# MD2020_02-08.net
KiCad netlist of a schematic drawn in EAGLE
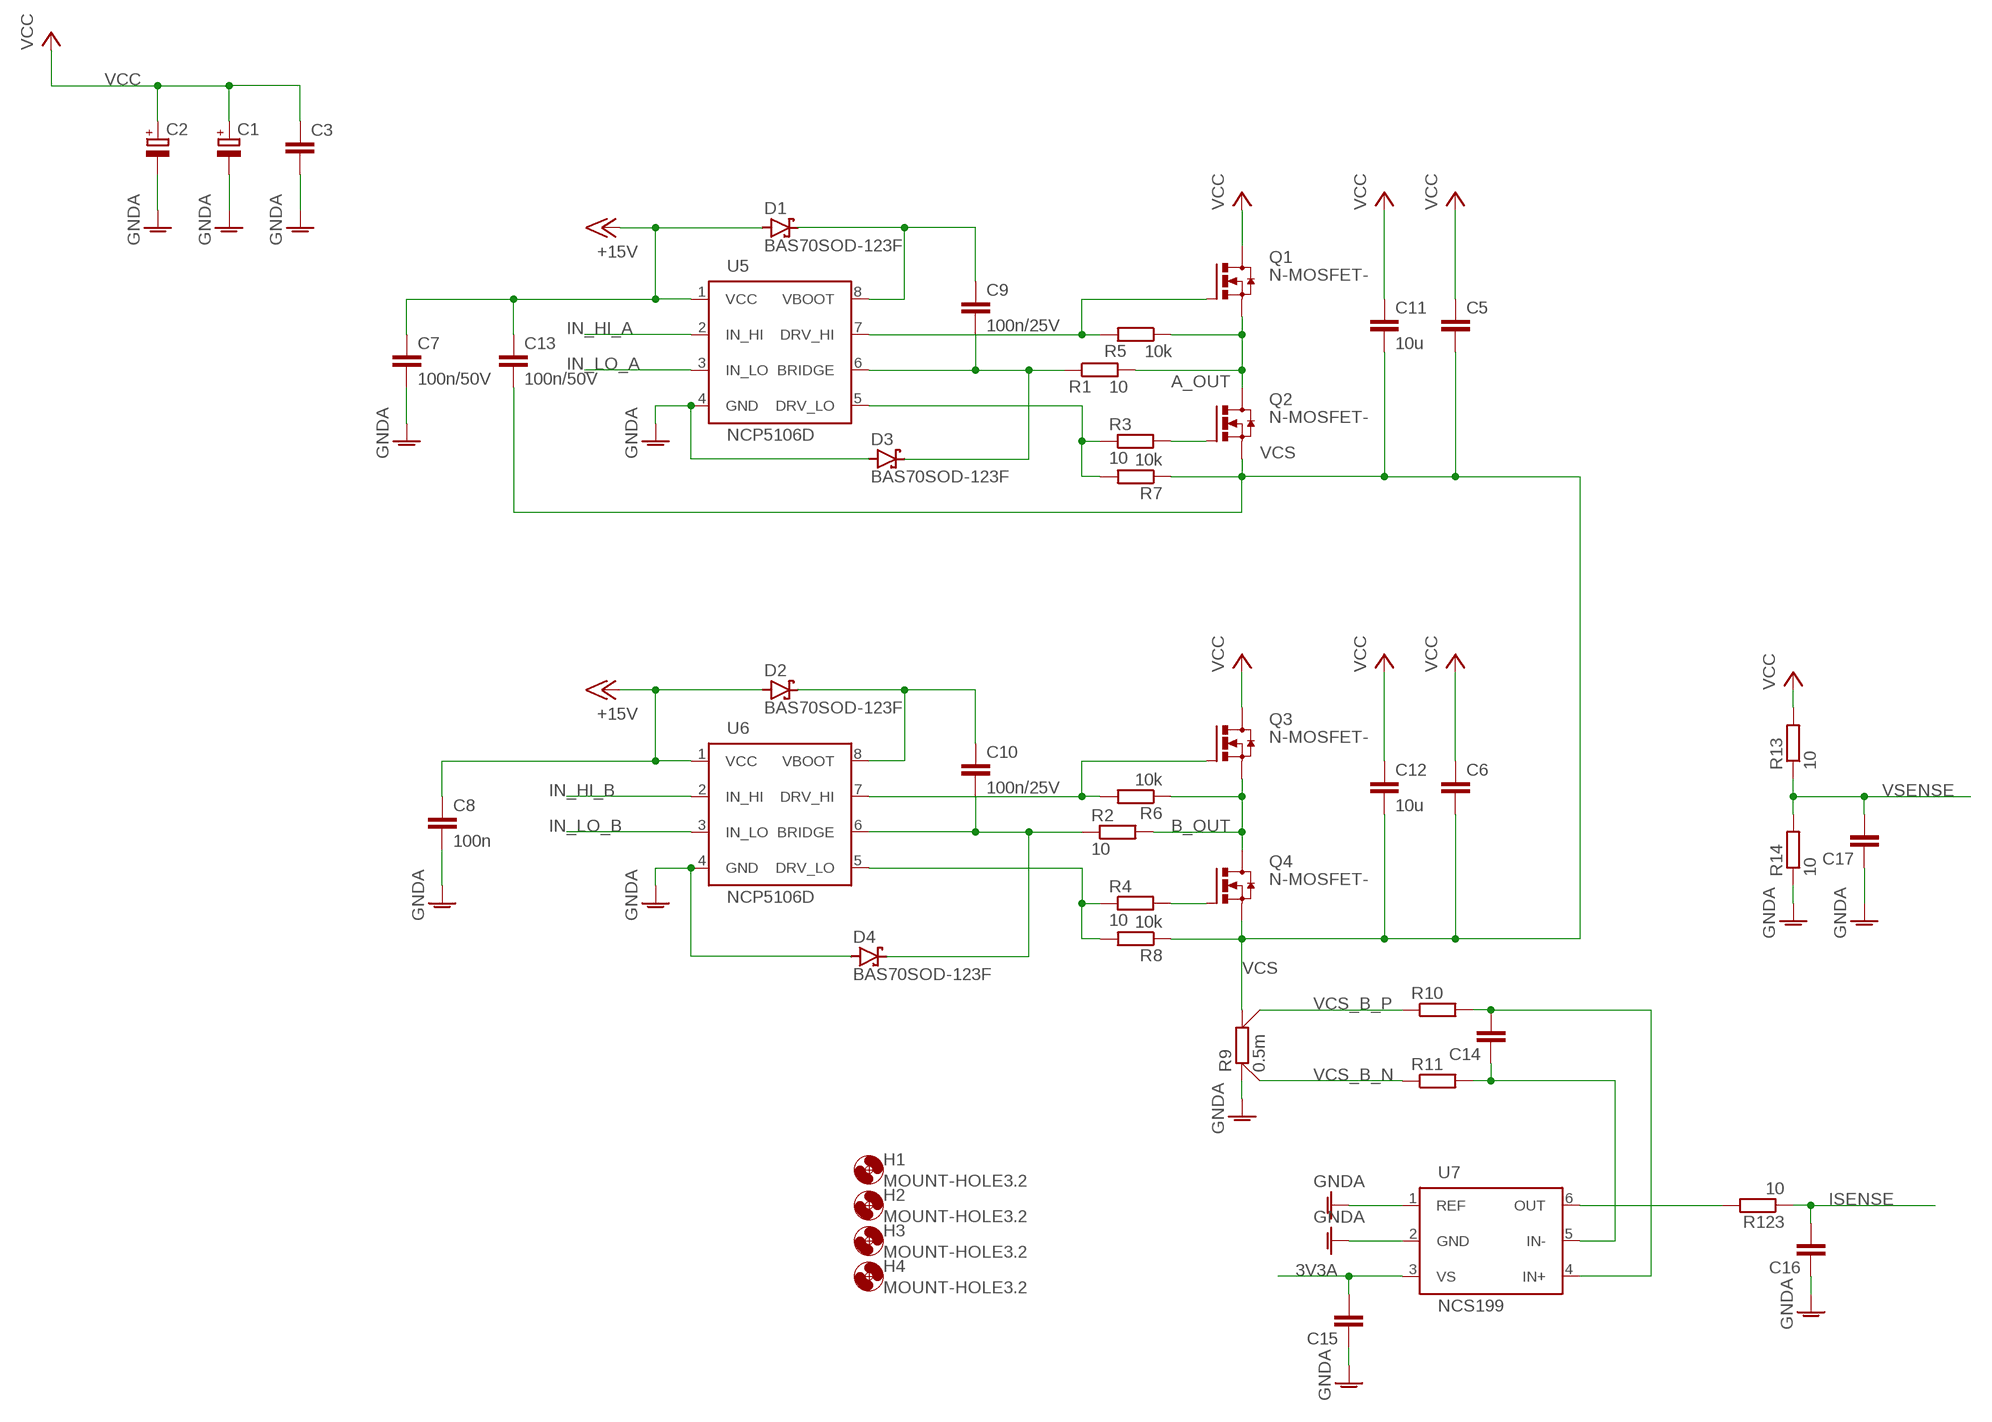
[diagram p0: schematic, sheet 1]
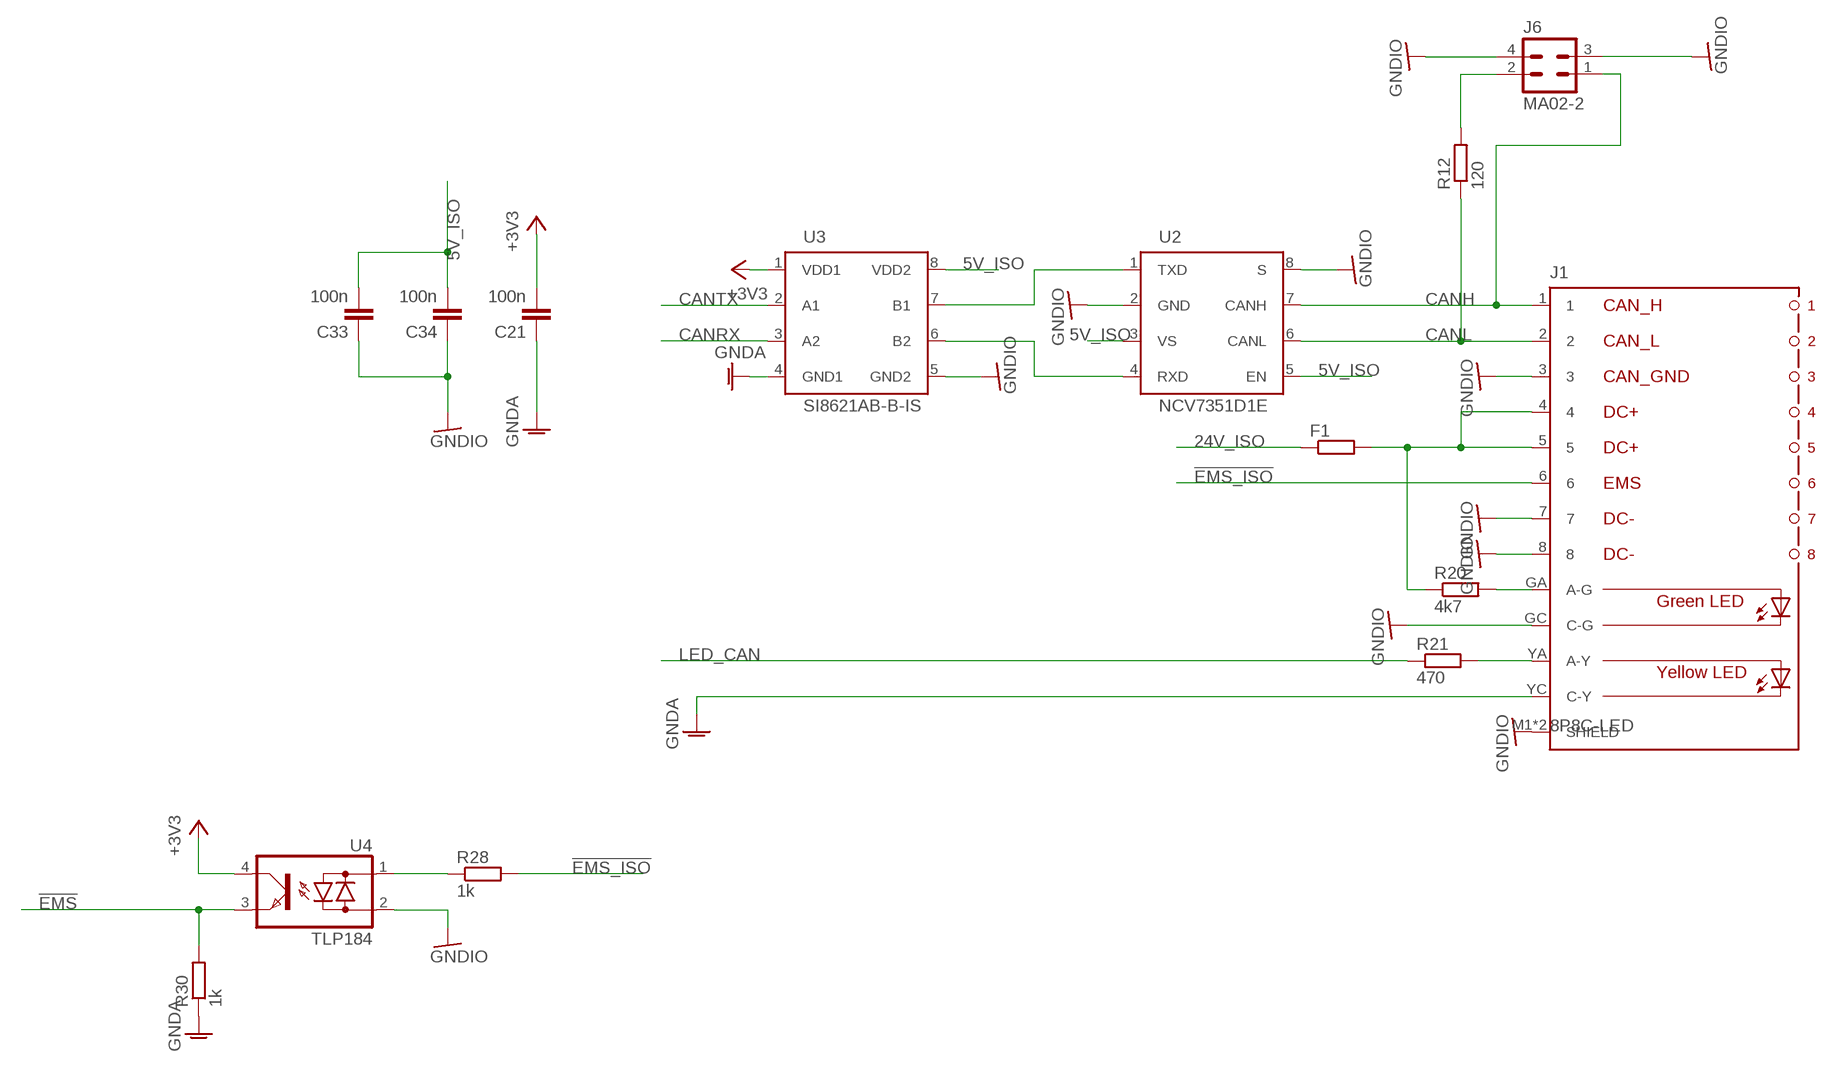
[diagram p1: schematic, sheet 2]
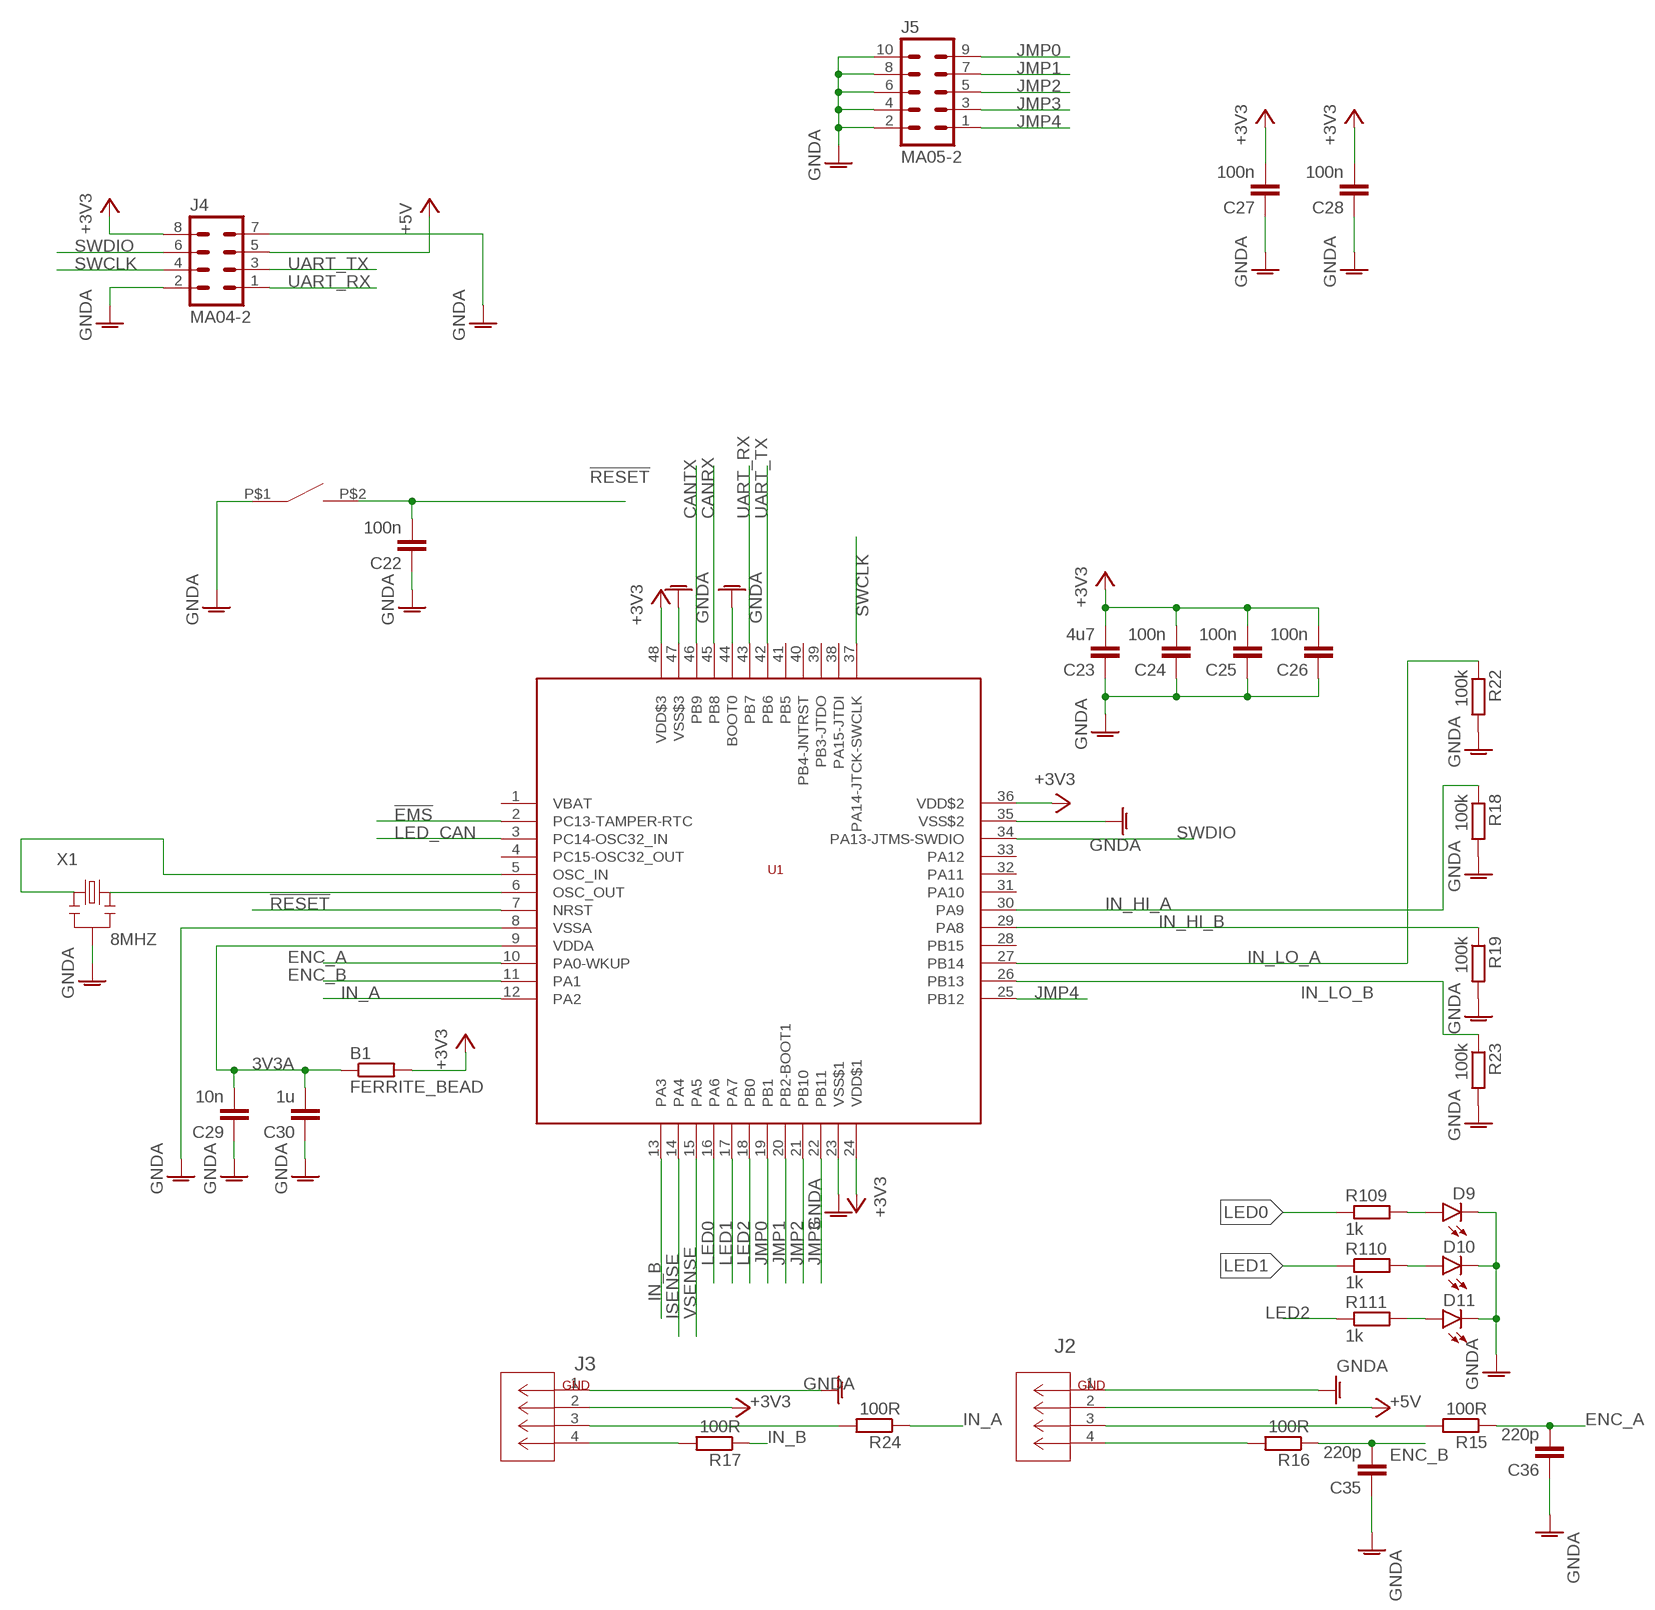
[diagram p2: schematic, sheet 3]
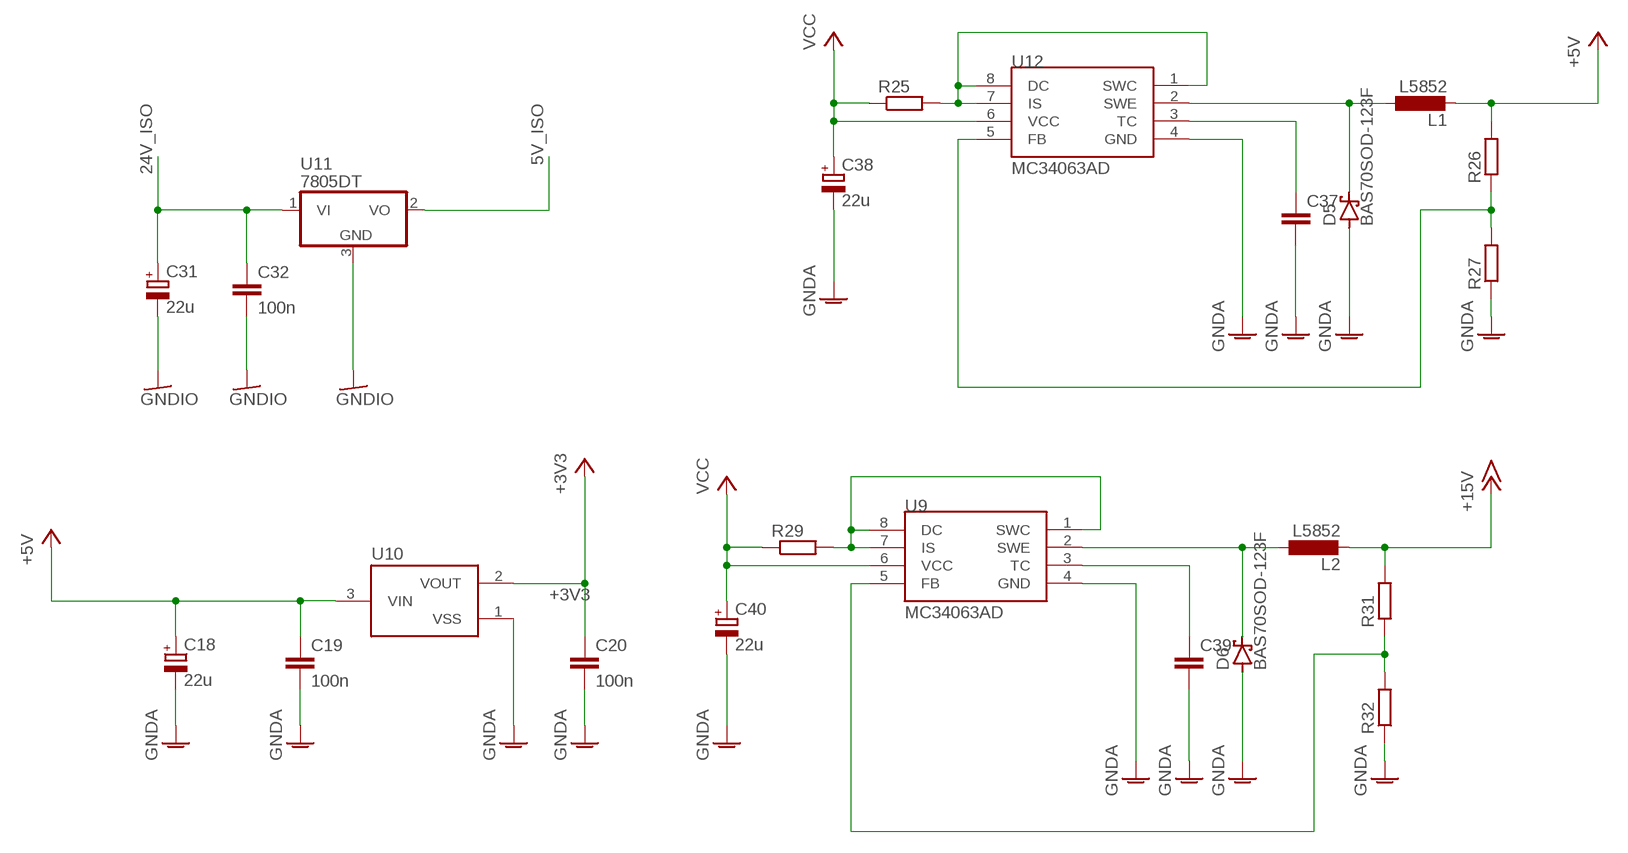
[diagram p3: schematic, sheet 4]

(export (version "E")
  (design (tool "Eeschema 10.0.6"))
  (components
    (comp (ref "C18")
      (value "22u")
      (footprint "eagle-import:E2,5-5")
      (libsource (lib "eagle-import") (part "CPOL-EUE2.5-5"))
    )
    (comp (ref "C19")
      (value "100n")
      (footprint "eagle-import:C0603")
      (libsource (lib "eagle-import") (part "C-EUC0603"))
    )
    (comp (ref "C20")
      (value "100n")
      (footprint "eagle-import:C0603")
      (libsource (lib "eagle-import") (part "C-EUC0603"))
    )
    (comp (ref "C31")
      (value "22u")
      (footprint "eagle-import:E2,5-5")
      (libsource (lib "eagle-import") (part "CPOL-EUE2.5-5"))
    )
    (comp (ref "C32")
      (value "100n")
      (footprint "eagle-import:C0603")
      (libsource (lib "eagle-import") (part "C-EUC0603"))
    )
    (comp (ref "C37")
      (value "C-EUC0603")
      (footprint "eagle-import:C0603")
      (libsource (lib "eagle-import") (part "rcl_334_C-EUC0603"))
    )
    (comp (ref "C38")
      (value "22u")
      (footprint "eagle-import:E2-5")
      (libsource (lib "eagle-import") (part "CPOL-EUE2-5"))
    )
    (comp (ref "C39")
      (value "C-EUC0603")
      (footprint "eagle-import:C0603")
      (libsource (lib "eagle-import") (part "rcl_334_C-EUC0603"))
    )
    (comp (ref "C40")
      (value "22u")
      (footprint "eagle-import:E2-5")
      (libsource (lib "eagle-import") (part "CPOL-EUE2-5"))
    )
    (comp (ref "D5")
      (value "BAS70SOD-123F")
      (footprint "eagle-import:SOD123F")
      (libsource (lib "eagle-import") (part "BAS70SOD-123F"))
    )
    (comp (ref "D6")
      (value "BAS70SOD-123F")
      (footprint "eagle-import:SOD123F")
      (libsource (lib "eagle-import") (part "BAS70SOD-123F"))
    )
    (comp (ref "L1")
      (value "L5852")
      (footprint "eagle-import:L5852")
      (libsource (lib "eagle-import") (part "L5852"))
    )
    (comp (ref "L2")
      (value "L5852")
      (footprint "eagle-import:L5852")
      (libsource (lib "eagle-import") (part "L5852"))
    )
    (comp (ref "R25")
      (value "R-EU_R0603")
      (footprint "eagle-import:R0603")
      (libsource (lib "eagle-import") (part "rcl_334_R-EU_R0603"))
    )
    (comp (ref "R26")
      (value "R-EU_R0603")
      (footprint "eagle-import:R0603")
      (libsource (lib "eagle-import") (part "rcl_334_R-EU_R0603"))
    )
    (comp (ref "R27")
      (value "R-EU_R0603")
      (footprint "eagle-import:R0603")
      (libsource (lib "eagle-import") (part "rcl_334_R-EU_R0603"))
    )
    (comp (ref "R29")
      (value "R-EU_R0603")
      (footprint "eagle-import:R0603")
      (libsource (lib "eagle-import") (part "rcl_334_R-EU_R0603"))
    )
    (comp (ref "R31")
      (value "R-EU_R0603")
      (footprint "eagle-import:R0603")
      (libsource (lib "eagle-import") (part "rcl_334_R-EU_R0603"))
    )
    (comp (ref "R32")
      (value "R-EU_R0603")
      (footprint "eagle-import:R0603")
      (libsource (lib "eagle-import") (part "rcl_334_R-EU_R0603"))
    )
    (comp (ref "U9")
      (value "MC34063AD")
      (footprint "eagle-import:SOIC8")
      (libsource (lib "eagle-import") (part "MC34063AD"))
    )
    (comp (ref "U10")
      (value "XC6206")
      (footprint "eagle-import:SOT95P240X110-3")
      (libsource (lib "eagle-import") (part "XC6206"))
    )
    (comp (ref "U11")
      (value "7805DT")
      (footprint "eagle-import:TO252")
      (libsource (lib "eagle-import") (part "78DT05"))
    )
    (comp (ref "U12")
      (value "MC34063AD")
      (footprint "eagle-import:SOIC8")
      (libsource (lib "eagle-import") (part "MC34063AD"))
    )
    (comp (ref "C1")
      (value "CPOL-EUE5-10.5")
      (footprint "eagle-import:E5-10,5")
      (libsource (lib "eagle-import") (part "CPOL-EUE5-10.5"))
    )
    (comp (ref "C2")
      (value "CPOL-EUE5-10.5")
      (footprint "eagle-import:E5-10,5")
      (libsource (lib "eagle-import") (part "CPOL-EUE5-10.5"))
    )
    (comp (ref "C3")
      (value "C-EUC0603")
      (footprint "eagle-import:C0603")
      (libsource (lib "eagle-import") (part "C-EUC0603"))
    )
    (comp (ref "C5")
      (value "C-EUC0603")
      (footprint "eagle-import:C0603")
      (libsource (lib "eagle-import") (part "C-EUC0603"))
    )
    (comp (ref "C6")
      (value "C-EUC0603")
      (footprint "eagle-import:C0603")
      (libsource (lib "eagle-import") (part "C-EUC0603"))
    )
    (comp (ref "C7")
      (value "100n/50V")
      (footprint "eagle-import:C0603")
      (libsource (lib "eagle-import") (part "C-EUC0603"))
    )
    (comp (ref "C8")
      (value "100n")
      (footprint "eagle-import:C0603")
      (libsource (lib "eagle-import") (part "C-EUC0603"))
    )
    (comp (ref "C9")
      (value "100n/25V")
      (footprint "eagle-import:C0603")
      (libsource (lib "eagle-import") (part "C-EUC0603"))
    )
    (comp (ref "C10")
      (value "100n/25V")
      (footprint "eagle-import:C0603")
      (libsource (lib "eagle-import") (part "C-EUC0603"))
    )
    (comp (ref "C11")
      (value "10u")
      (footprint "eagle-import:C1210")
      (libsource (lib "eagle-import") (part "C-EUC1210"))
    )
    (comp (ref "C12")
      (value "10u")
      (footprint "eagle-import:C1210")
      (libsource (lib "eagle-import") (part "C-EUC1210"))
    )
    (comp (ref "C13")
      (value "100n/50V")
      (footprint "eagle-import:C0603")
      (libsource (lib "eagle-import") (part "C-EUC0603"))
    )
    (comp (ref "C14")
      (value "C-EUC0603")
      (footprint "eagle-import:C0603")
      (libsource (lib "eagle-import") (part "rcl_334_C-EUC0603"))
    )
    (comp (ref "C15")
      (value "C-EUC0603")
      (footprint "eagle-import:C0603")
      (libsource (lib "eagle-import") (part "rcl_334_C-EUC0603"))
    )
    (comp (ref "C16")
      (value "C-EUC0603")
      (footprint "eagle-import:C0603")
      (libsource (lib "eagle-import") (part "rcl_334_C-EUC0603"))
    )
    (comp (ref "C17")
      (value "C-EUC0603")
      (footprint "eagle-import:C0603")
      (libsource (lib "eagle-import") (part "rcl_334_C-EUC0603"))
    )
    (comp (ref "D1")
      (value "BAS70SOD-123F")
      (footprint "eagle-import:SOD123F")
      (libsource (lib "eagle-import") (part "BAS70SOD-123F"))
    )
    (comp (ref "D2")
      (value "BAS70SOD-123F")
      (footprint "eagle-import:SOD123F")
      (libsource (lib "eagle-import") (part "BAS70SOD-123F"))
    )
    (comp (ref "D3")
      (value "BAS70SOD-123F")
      (footprint "eagle-import:SOD123F")
      (libsource (lib "eagle-import") (part "BAS70SOD-123F"))
    )
    (comp (ref "D4")
      (value "BAS70SOD-123F")
      (footprint "eagle-import:SOD123F")
      (libsource (lib "eagle-import") (part "BAS70SOD-123F"))
    )
    (comp (ref "H1")
      (value "MOUNT-HOLE3.2")
      (footprint "eagle-import:3,2")
      (libsource (lib "eagle-import") (part "MOUNT-HOLE3.2"))
    )
    (comp (ref "H2")
      (value "MOUNT-HOLE3.2")
      (footprint "eagle-import:3,2")
      (libsource (lib "eagle-import") (part "MOUNT-HOLE3.2"))
    )
    (comp (ref "H3")
      (value "MOUNT-HOLE3.2")
      (footprint "eagle-import:3,2")
      (libsource (lib "eagle-import") (part "MOUNT-HOLE3.2"))
    )
    (comp (ref "H4")
      (value "MOUNT-HOLE3.2")
      (footprint "eagle-import:3,2")
      (libsource (lib "eagle-import") (part "MOUNT-HOLE3.2"))
    )
    (comp (ref "Q1")
      (value "N-MOSFET-")
      (footprint "eagle-import:SOT669")
      (libsource (lib "eagle-import") (part "N-MOSFET-"))
    )
    (comp (ref "Q2")
      (value "N-MOSFET-")
      (footprint "eagle-import:SOT669")
      (libsource (lib "eagle-import") (part "N-MOSFET-"))
    )
    (comp (ref "Q3")
      (value "N-MOSFET-")
      (footprint "eagle-import:SOT669")
      (libsource (lib "eagle-import") (part "N-MOSFET-"))
    )
    (comp (ref "Q4")
      (value "N-MOSFET-")
      (footprint "eagle-import:SOT669")
      (libsource (lib "eagle-import") (part "N-MOSFET-"))
    )
    (comp (ref "R1")
      (value "10")
      (footprint "eagle-import:R0603")
      (libsource (lib "eagle-import") (part "R-EU_R0603"))
    )
    (comp (ref "R2")
      (value "10")
      (footprint "eagle-import:R0603")
      (libsource (lib "eagle-import") (part "R-EU_R0603"))
    )
    (comp (ref "R3")
      (value "10")
      (footprint "eagle-import:R0603")
      (libsource (lib "eagle-import") (part "R-EU_R0603"))
    )
    (comp (ref "R4")
      (value "10")
      (footprint "eagle-import:R0603")
      (libsource (lib "eagle-import") (part "R-EU_R0603"))
    )
    (comp (ref "R5")
      (value "10k")
      (footprint "eagle-import:R0603")
      (libsource (lib "eagle-import") (part "R-EU_R0603"))
    )
    (comp (ref "R6")
      (value "10k")
      (footprint "eagle-import:R0603")
      (libsource (lib "eagle-import") (part "R-EU_R0603"))
    )
    (comp (ref "R7")
      (value "10k")
      (footprint "eagle-import:R0603")
      (libsource (lib "eagle-import") (part "R-EU_R0603"))
    )
    (comp (ref "R8")
      (value "10k")
      (footprint "eagle-import:R0603")
      (libsource (lib "eagle-import") (part "R-EU_R0603"))
    )
    (comp (ref "R9")
      (value "0.5m")
      (footprint "eagle-import:CSS2H-2512")
      (libsource (lib "eagle-import") (part "CSS2H-2512"))
    )
    (comp (ref "R10")
      (value "R-EU_R0603")
      (footprint "eagle-import:R0603")
      (libsource (lib "eagle-import") (part "rcl_334_R-EU_R0603"))
    )
    (comp (ref "R11")
      (value "R-EU_R0603")
      (footprint "eagle-import:R0603")
      (libsource (lib "eagle-import") (part "rcl_334_R-EU_R0603"))
    )
    (comp (ref "R13")
      (value "10")
      (footprint "eagle-import:R0603")
      (libsource (lib "eagle-import") (part "R-EU_R0603"))
    )
    (comp (ref "R14")
      (value "10")
      (footprint "eagle-import:R0603")
      (libsource (lib "eagle-import") (part "R-EU_R0603"))
    )
    (comp (ref "R123")
      (value "10")
      (footprint "eagle-import:R0603")
      (libsource (lib "eagle-import") (part "R-EU_R0603"))
    )
    (comp (ref "U5")
      (value "NCP5106D")
      (footprint "eagle-import:SOIC127P600X175-8")
      (libsource (lib "eagle-import") (part "NCP5106D"))
    )
    (comp (ref "U6")
      (value "NCP5106D")
      (footprint "eagle-import:SOIC127P600X175-8")
      (libsource (lib "eagle-import") (part "NCP5106D"))
    )
    (comp (ref "U7")
      (value "NCS199")
      (footprint "eagle-import:SOT65P210X110-6")
      (libsource (lib "eagle-import") (part "NCS199"))
    )
    (comp (ref "B1")
      (value "FERRITE_BEAD")
      (footprint "eagle-import:R0603")
      (libsource (lib "eagle-import") (part "R-EU_R0603"))
    )
    (comp (ref "C22")
      (value "100n")
      (footprint "eagle-import:C0603")
      (libsource (lib "eagle-import") (part "C-EUC0603"))
    )
    (comp (ref "C23")
      (value "4u7")
      (footprint "eagle-import:C0805")
      (libsource (lib "eagle-import") (part "C-EUC0805"))
    )
    (comp (ref "C24")
      (value "100n")
      (footprint "eagle-import:C0603")
      (libsource (lib "eagle-import") (part "C-EUC0603"))
    )
    (comp (ref "C25")
      (value "100n")
      (footprint "eagle-import:C0603")
      (libsource (lib "eagle-import") (part "C-EUC0603"))
    )
    (comp (ref "C26")
      (value "100n")
      (footprint "eagle-import:C0603")
      (libsource (lib "eagle-import") (part "C-EUC0603"))
    )
    (comp (ref "C27")
      (value "100n")
      (footprint "eagle-import:C0603")
      (libsource (lib "eagle-import") (part "C-EUC0603"))
    )
    (comp (ref "C28")
      (value "100n")
      (footprint "eagle-import:C0603")
      (libsource (lib "eagle-import") (part "C-EUC0603"))
    )
    (comp (ref "C29")
      (value "10n")
      (footprint "eagle-import:C0603")
      (libsource (lib "eagle-import") (part "C-EUC0603"))
    )
    (comp (ref "C30")
      (value "1u")
      (footprint "eagle-import:C0603")
      (libsource (lib "eagle-import") (part "C-EUC0603"))
    )
    (comp (ref "C35")
      (value "220p")
      (footprint "eagle-import:C0603")
      (libsource (lib "eagle-import") (part "C-EUC0603"))
    )
    (comp (ref "C36")
      (value "220p")
      (footprint "eagle-import:C0603")
      (libsource (lib "eagle-import") (part "C-EUC0603"))
    )
    (comp (ref "D9")
      (value "LEDCHIPLED_0805")
      (footprint "eagle-import:CHIPLED_0805")
      (libsource (lib "eagle-import") (part "LEDCHIPLED_0805"))
    )
    (comp (ref "D10")
      (value "LEDCHIPLED_0805")
      (footprint "eagle-import:CHIPLED_0805")
      (libsource (lib "eagle-import") (part "LEDCHIPLED_0805"))
    )
    (comp (ref "D11")
      (value "LEDCHIPLED_0805")
      (footprint "eagle-import:CHIPLED_0805")
      (libsource (lib "eagle-import") (part "LEDCHIPLED_0805"))
    )
    (comp (ref "J2")
      (value "1744426-4")
      (footprint "eagle-import:CONN4_1744426-4")
      (fields (field (name "MANUFACTURER_PART_NUMBER") "17444264"))
      (libsource (lib "eagle-import") (part "1744426-4"))
    )
    (comp (ref "J3")
      (value "1744426-4")
      (footprint "eagle-import:CONN4_1744426-4")
      (fields (field (name "MANUFACTURER_PART_NUMBER") "17444264"))
      (libsource (lib "eagle-import") (part "1744426-4"))
    )
    (comp (ref "J4")
      (value "MA04-2")
      (footprint "eagle-import:MA04-2W")
      (libsource (lib "eagle-import") (part "MA04-2"))
    )
    (comp (ref "J5")
      (value "MA05-2")
      (footprint "eagle-import:MA05-2W")
      (libsource (lib "eagle-import") (part "MA05-2"))
    )
    (comp (ref "R15")
      (value "100R")
      (footprint "eagle-import:R0603")
      (libsource (lib "eagle-import") (part "R-EU_R0603"))
    )
    (comp (ref "R16")
      (value "100R")
      (footprint "eagle-import:R0603")
      (libsource (lib "eagle-import") (part "R-EU_R0603"))
    )
    (comp (ref "R17")
      (value "100R")
      (footprint "eagle-import:R0603")
      (libsource (lib "eagle-import") (part "R-EU_R0603"))
    )
    (comp (ref "R18")
      (value "100k")
      (footprint "eagle-import:R0603")
      (libsource (lib "eagle-import") (part "R-EU_R0603"))
    )
    (comp (ref "R19")
      (value "100k")
      (footprint "eagle-import:R0603")
      (libsource (lib "eagle-import") (part "R-EU_R0603"))
    )
    (comp (ref "R22")
      (value "100k")
      (footprint "eagle-import:R0603")
      (libsource (lib "eagle-import") (part "R-EU_R0603"))
    )
    (comp (ref "R23")
      (value "100k")
      (footprint "eagle-import:R0603")
      (libsource (lib "eagle-import") (part "R-EU_R0603"))
    )
    (comp (ref "R24")
      (value "100R")
      (footprint "eagle-import:R0603")
      (libsource (lib "eagle-import") (part "R-EU_R0603"))
    )
    (comp (ref "R109")
      (value "1k")
      (footprint "eagle-import:R0603")
      (libsource (lib "eagle-import") (part "R-EU_R0603"))
    )
    (comp (ref "R110")
      (value "1k")
      (footprint "eagle-import:R0603")
      (libsource (lib "eagle-import") (part "R-EU_R0603"))
    )
    (comp (ref "R111")
      (value "1k")
      (footprint "eagle-import:R0603")
      (libsource (lib "eagle-import") (part "R-EU_R0603"))
    )
    (comp (ref "S1")
      (value "SWITCH_TACTILETOP")
      (footprint "eagle-import:SWITCH_TACTILE_3X6")
      (libsource (lib "eagle-import") (part "SWITCH_TACTILETOP"))
    )
    (comp (ref "U1")
      (value "STM32F103C8")
      (footprint "eagle-import:LQFP48")
      (libsource (lib "eagle-import") (part "STM32F103C8"))
    )
    (comp (ref "X1")
      (value "8MHZ")
      (footprint "eagle-import:X3-SMD-3.6X1.3X0.8MM")
      (libsource (lib "eagle-import") (part "SMD-CRYSTAL-8MHZ--0.3%-150R(3P-3.6X1.3MM)"))
    )
    (comp (ref "C21")
      (value "100n")
      (footprint "eagle-import:C0603")
      (libsource (lib "eagle-import") (part "C-EUC0603"))
    )
    (comp (ref "C33")
      (value "100n")
      (footprint "eagle-import:C0805")
      (libsource (lib "eagle-import") (part "C-EUC0805"))
    )
    (comp (ref "C34")
      (value "100n")
      (footprint "eagle-import:C0603")
      (libsource (lib "eagle-import") (part "C-EUC0603"))
    )
    (comp (ref "F1")
      (value "R-EU_R1206")
      (footprint "eagle-import:R1206")
      (libsource (lib "eagle-import") (part "rcl_334_R-EU_R1206"))
    )
    (comp (ref "J1")
      (value "8P8C-LED")
      (footprint "eagle-import:8P8C-LED")
      (libsource (lib "eagle-import") (part "8P8C-LED"))
    )
    (comp (ref "J6")
      (value "MA02-2")
      (footprint "eagle-import:MA02-2W")
      (libsource (lib "eagle-import") (part "MA02-2"))
    )
    (comp (ref "R12")
      (value "120")
      (footprint "eagle-import:R0603")
      (libsource (lib "eagle-import") (part "rcl_334_R-EU_R0603"))
    )
    (comp (ref "R20")
      (value "4k7")
      (footprint "eagle-import:R0603")
      (libsource (lib "eagle-import") (part "rcl_334_R-EU_R0603"))
    )
    (comp (ref "R21")
      (value "470")
      (footprint "eagle-import:R0603")
      (libsource (lib "eagle-import") (part "rcl_334_R-EU_R0603"))
    )
    (comp (ref "R28")
      (value "1k")
      (footprint "eagle-import:R0603")
      (libsource (lib "eagle-import") (part "rcl_334_R-EU_R0603"))
    )
    (comp (ref "R30")
      (value "1k")
      (footprint "eagle-import:R0603")
      (libsource (lib "eagle-import") (part "rcl_334_R-EU_R0603"))
    )
    (comp (ref "U2")
      (value "NCV7351D1E")
      (footprint "eagle-import:SO08")
      (libsource (lib "eagle-import") (part "NCV7351D1E"))
    )
    (comp (ref "U3")
      (value "SI8621AB-B-IS")
      (footprint "eagle-import:SO08")
      (libsource (lib "eagle-import") (part "SI8621AB-B-IS"))
    )
    (comp (ref "U4")
      (value "TLP184")
      (footprint "eagle-import:11-4M1S")
      (libsource (lib "eagle-import") (part "TLP184"))
    )
  )
  (nets
    (net (code "1") (name "+3V3") (class "Default")
      (node (ref "B1") (pin "2") (pinfunction "2_2") (pintype "passive"))
      (node (ref "C20") (pin "1") (pinfunction "1_1") (pintype "passive"))
      (node (ref "C21") (pin "2") (pinfunction "2_2") (pintype "passive"))
      (node (ref "C23") (pin "2") (pinfunction "2_2") (pintype "passive"))
      (node (ref "C24") (pin "2") (pinfunction "2_2") (pintype "passive"))
      (node (ref "C25") (pin "2") (pinfunction "2_2") (pintype "passive"))
      (node (ref "C26") (pin "2") (pinfunction "2_2") (pintype "passive"))
      (node (ref "C27") (pin "2") (pinfunction "2_2") (pintype "passive"))
      (node (ref "C28") (pin "2") (pinfunction "2_2") (pintype "passive"))
      (node (ref "J3") (pin "2") (pinfunction "2_2") (pintype "passive"))
      (node (ref "J4") (pin "8") (pinfunction "8_8") (pintype "passive"))
      (node (ref "U1") (pin "24") (pinfunction "VDD$1_24") (pintype "passive"))
      (node (ref "U1") (pin "36") (pinfunction "VDD$2_36") (pintype "passive"))
      (node (ref "U1") (pin "48") (pinfunction "VDD$3_48") (pintype "passive"))
      (node (ref "U10") (pin "2") (pinfunction "VOUT_2") (pintype "bidirectional"))
      (node (ref "U3") (pin "1") (pinfunction "VDD1_1") (pintype "power_in"))
      (node (ref "U4") (pin "4") (pinfunction "C_4") (pintype "passive"))
    )
    (net (code "2") (name "+5V") (class "Default")
      (node (ref "C18") (pin "+") (pinfunction "+_+") (pintype "passive"))
      (node (ref "C19") (pin "1") (pinfunction "1_1") (pintype "passive"))
      (node (ref "J2") (pin "2") (pinfunction "2_2") (pintype "passive"))
      (node (ref "J4") (pin "5") (pinfunction "5_5") (pintype "passive"))
      (node (ref "L1") (pin "P$2") (pinfunction "2_P$2") (pintype "passive"))
      (node (ref "R26") (pin "2") (pinfunction "2_2") (pintype "passive"))
      (node (ref "U10") (pin "3") (pinfunction "VIN_3") (pintype "bidirectional"))
    )
    (net (code "3") (name "+15V") (class "Default")
      (node (ref "C13") (pin "1") (pinfunction "1_1") (pintype "passive"))
      (node (ref "C7") (pin "1") (pinfunction "1_1") (pintype "passive"))
      (node (ref "C8") (pin "1") (pinfunction "1_1") (pintype "passive"))
      (node (ref "D1") (pin "A") (pinfunction "A_A") (pintype "passive"))
      (node (ref "D2") (pin "A") (pinfunction "A_A") (pintype "passive"))
      (node (ref "L2") (pin "P$2") (pinfunction "2_P$2") (pintype "passive"))
      (node (ref "R31") (pin "2") (pinfunction "2_2") (pintype "passive"))
      (node (ref "U5") (pin "1") (pinfunction "VCC_1") (pintype "power_in"))
      (node (ref "U6") (pin "1") (pinfunction "VCC_1") (pintype "power_in"))
    )
    (net (code "4") (name "3V3A") (class "Default")
      (node (ref "B1") (pin "1") (pinfunction "1_1") (pintype "passive"))
      (node (ref "C15") (pin "2") (pinfunction "2_2") (pintype "passive"))
      (node (ref "C29") (pin "2") (pinfunction "2_2") (pintype "passive"))
      (node (ref "C30") (pin "2") (pinfunction "2_2") (pintype "passive"))
      (node (ref "U1") (pin "9") (pinfunction "VDDA_9") (pintype "bidirectional"))
      (node (ref "U7") (pin "3") (pinfunction "VS_3") (pintype "power_in"))
    )
    (net (code "5") (name "5V_ISO") (class "Default")
      (node (ref "C33") (pin "2") (pinfunction "2_2") (pintype "passive"))
      (node (ref "C34") (pin "2") (pinfunction "2_2") (pintype "passive"))
      (node (ref "U11") (pin "2") (pinfunction "VO_2") (pintype "passive"))
      (node (ref "U2") (pin "3") (pinfunction "VS_3") (pintype "power_in"))
      (node (ref "U2") (pin "5") (pinfunction "EN_5") (pintype "input"))
      (node (ref "U3") (pin "8") (pinfunction "VDD2_8") (pintype "power_in"))
    )
    (net (code "6") (name "24V_ISO") (class "Default")
      (node (ref "C31") (pin "+") (pinfunction "+_+") (pintype "passive"))
      (node (ref "C32") (pin "1") (pinfunction "1_1") (pintype "passive"))
      (node (ref "F1") (pin "1") (pinfunction "1_1") (pintype "passive"))
      (node (ref "U11") (pin "1") (pinfunction "VI_1") (pintype "input"))
    )
    (net (code "7") (name "A_OUT") (class "Default")
      (node (ref "Q1") (pin "1") (pinfunction "SOURCE_1") (pintype "passive"))
      (node (ref "Q1") (pin "2") (pinfunction "SOURCE_2") (pintype "passive"))
      (node (ref "Q1") (pin "3") (pinfunction "SOURCE_3") (pintype "passive"))
      (node (ref "Q2") (pin "5") (pinfunction "DRAIN_5") (pintype "passive"))
      (node (ref "R1") (pin "2") (pinfunction "2_2") (pintype "passive"))
      (node (ref "R5") (pin "1") (pinfunction "1_1") (pintype "passive"))
    )
    (net (code "8") (name "B_OUT") (class "Default")
      (node (ref "Q3") (pin "1") (pinfunction "SOURCE_1") (pintype "passive"))
      (node (ref "Q3") (pin "2") (pinfunction "SOURCE_2") (pintype "passive"))
      (node (ref "Q3") (pin "3") (pinfunction "SOURCE_3") (pintype "passive"))
      (node (ref "Q4") (pin "5") (pinfunction "DRAIN_5") (pintype "passive"))
      (node (ref "R2") (pin "2") (pinfunction "2_2") (pintype "passive"))
      (node (ref "R6") (pin "1") (pinfunction "1_1") (pintype "passive"))
    )
    (net (code "9") (name "CANH") (class "Default")
      (node (ref "J1") (pin "1") (pinfunction "1_1") (pintype "input"))
      (node (ref "J6") (pin "1") (pinfunction "1_1") (pintype "passive"))
      (node (ref "U2") (pin "7") (pinfunction "CANH_7") (pintype "output"))
    )
    (net (code "10") (name "CANL") (class "Default")
      (node (ref "J1") (pin "2") (pinfunction "2_2") (pintype "input"))
      (node (ref "R12") (pin "1") (pinfunction "1_1") (pintype "passive"))
      (node (ref "U2") (pin "6") (pinfunction "CANL_6") (pintype "output"))
    )
    (net (code "11") (name "CANRX") (class "Default")
      (node (ref "U1") (pin "45") (pinfunction "PB8_45") (pintype "bidirectional"))
      (node (ref "U3") (pin "3") (pinfunction "A2_3") (pintype "output"))
    )
    (net (code "12") (name "CANTX") (class "Default")
      (node (ref "U1") (pin "46") (pinfunction "PB9_46") (pintype "bidirectional"))
      (node (ref "U3") (pin "2") (pinfunction "A1_2") (pintype "input"))
    )
    (net (code "13") (name "ENC_A") (class "Default")
      (node (ref "C36") (pin "2") (pinfunction "2_2") (pintype "passive"))
      (node (ref "R15") (pin "1") (pinfunction "1_1") (pintype "passive"))
      (node (ref "U1") (pin "10") (pinfunction "PA0-WKUP_10") (pintype "bidirectional"))
    )
    (net (code "14") (name "ENC_B") (class "Default")
      (node (ref "C35") (pin "2") (pinfunction "2_2") (pintype "passive"))
      (node (ref "R16") (pin "1") (pinfunction "1_1") (pintype "passive"))
      (node (ref "U1") (pin "11") (pinfunction "PA1_11") (pintype "bidirectional"))
    )
    (net (code "15") (name "GNDA") (class "Default")
      (node (ref "C1") (pin "-") (pinfunction "-_-") (pintype "passive"))
      (node (ref "C15") (pin "1") (pinfunction "1_1") (pintype "passive"))
      (node (ref "C16") (pin "1") (pinfunction "1_1") (pintype "passive"))
      (node (ref "C17") (pin "1") (pinfunction "1_1") (pintype "passive"))
      (node (ref "C18") (pin "-") (pinfunction "-_-") (pintype "passive"))
      (node (ref "C19") (pin "2") (pinfunction "2_2") (pintype "passive"))
      (node (ref "C2") (pin "-") (pinfunction "-_-") (pintype "passive"))
      (node (ref "C20") (pin "2") (pinfunction "2_2") (pintype "passive"))
      (node (ref "C21") (pin "1") (pinfunction "1_1") (pintype "passive"))
      (node (ref "C22") (pin "1") (pinfunction "1_1") (pintype "passive"))
      (node (ref "C23") (pin "1") (pinfunction "1_1") (pintype "passive"))
      (node (ref "C24") (pin "1") (pinfunction "1_1") (pintype "passive"))
      (node (ref "C25") (pin "1") (pinfunction "1_1") (pintype "passive"))
      (node (ref "C26") (pin "1") (pinfunction "1_1") (pintype "passive"))
      (node (ref "C27") (pin "1") (pinfunction "1_1") (pintype "passive"))
      (node (ref "C28") (pin "1") (pinfunction "1_1") (pintype "passive"))
      (node (ref "C29") (pin "1") (pinfunction "1_1") (pintype "passive"))
      (node (ref "C3") (pin "2") (pinfunction "2_2") (pintype "passive"))
      (node (ref "C30") (pin "1") (pinfunction "1_1") (pintype "passive"))
      (node (ref "C35") (pin "1") (pinfunction "1_1") (pintype "passive"))
      (node (ref "C36") (pin "1") (pinfunction "1_1") (pintype "passive"))
      (node (ref "C37") (pin "2") (pinfunction "2_2") (pintype "passive"))
      (node (ref "C38") (pin "-") (pinfunction "-_-") (pintype "passive"))
      (node (ref "C39") (pin "2") (pinfunction "2_2") (pintype "passive"))
      (node (ref "C40") (pin "-") (pinfunction "-_-") (pintype "passive"))
      (node (ref "C7") (pin "2") (pinfunction "2_2") (pintype "passive"))
      (node (ref "C8") (pin "2") (pinfunction "2_2") (pintype "passive"))
      (node (ref "D10") (pin "C") (pinfunction "C_C") (pintype "passive"))
      (node (ref "D11") (pin "C") (pinfunction "C_C") (pintype "passive"))
      (node (ref "D3") (pin "A") (pinfunction "A_A") (pintype "passive"))
      (node (ref "D4") (pin "A") (pinfunction "A_A") (pintype "passive"))
      (node (ref "D5") (pin "A") (pinfunction "A_A") (pintype "passive"))
      (node (ref "D6") (pin "A") (pinfunction "A_A") (pintype "passive"))
      (node (ref "D9") (pin "C") (pinfunction "C_C") (pintype "passive"))
      (node (ref "J1") (pin "YC") (pinfunction "C-Y_YC") (pintype "passive"))
      (node (ref "J2") (pin "1") (pinfunction "1_1") (pintype "passive"))
      (node (ref "J3") (pin "1") (pinfunction "1_1") (pintype "passive"))
      (node (ref "J4") (pin "2") (pinfunction "2_2") (pintype "passive"))
      (node (ref "J4") (pin "7") (pinfunction "7_7") (pintype "passive"))
      (node (ref "J5") (pin "10") (pinfunction "10_10") (pintype "passive"))
      (node (ref "J5") (pin "2") (pinfunction "2_2") (pintype "passive"))
      (node (ref "J5") (pin "4") (pinfunction "4_4") (pintype "passive"))
      (node (ref "J5") (pin "6") (pinfunction "6_6") (pintype "passive"))
      (node (ref "J5") (pin "8") (pinfunction "8_8") (pintype "passive"))
      (node (ref "R14") (pin "1") (pinfunction "1_1") (pintype "passive"))
      (node (ref "R18") (pin "2") (pinfunction "2_2") (pintype "passive"))
      (node (ref "R19") (pin "2") (pinfunction "2_2") (pintype "passive"))
      (node (ref "R22") (pin "2") (pinfunction "2_2") (pintype "passive"))
      (node (ref "R23") (pin "2") (pinfunction "2_2") (pintype "passive"))
      (node (ref "R27") (pin "1") (pinfunction "1_1") (pintype "passive"))
      (node (ref "R30") (pin "1") (pinfunction "1_1") (pintype "passive"))
      (node (ref "R32") (pin "1") (pinfunction "1_1") (pintype "passive"))
      (node (ref "R9") (pin "1$1") (pinfunction "1_1$1") (pintype "passive"))
      (node (ref "R9") (pin "1$2") (pinfunction "1_1$2") (pintype "passive"))
      (node (ref "S1") (pin "P$1") (pinfunction "1_P$1") (pintype "bidirectional"))
      (node (ref "U1") (pin "23") (pinfunction "VSS$1_23") (pintype "passive"))
      (node (ref "U1") (pin "35") (pinfunction "VSS$2_35") (pintype "passive"))
      (node (ref "U1") (pin "44") (pinfunction "BOOT0_44") (pintype "input"))
      (node (ref "U1") (pin "47") (pinfunction "VSS$3_47") (pintype "passive"))
      (node (ref "U1") (pin "8") (pinfunction "VSSA_8") (pintype "bidirectional"))
      (node (ref "U10") (pin "1") (pinfunction "VSS_1") (pintype "bidirectional"))
      (node (ref "U12") (pin "4") (pinfunction "GND_4") (pintype "passive"))
      (node (ref "U3") (pin "4") (pinfunction "GND1_4") (pintype "power_in"))
      (node (ref "U5") (pin "4") (pinfunction "GND_4") (pintype "power_in"))
      (node (ref "U6") (pin "4") (pinfunction "GND_4") (pintype "power_in"))
      (node (ref "U7") (pin "1") (pinfunction "REF_1") (pintype "power_in"))
      (node (ref "U7") (pin "2") (pinfunction "GND_2") (pintype "power_in"))
      (node (ref "U9") (pin "4") (pinfunction "GND_4") (pintype "passive"))
      (node (ref "X1") (pin "2") (pinfunction "2_2") (pintype "passive"))
    )
    (net (code "16") (name "GNDIO") (class "Default")
      (node (ref "C31") (pin "-") (pinfunction "-_-") (pintype "passive"))
      (node (ref "C32") (pin "2") (pinfunction "2_2") (pintype "passive"))
      (node (ref "C33") (pin "1") (pinfunction "1_1") (pintype "passive"))
      (node (ref "C34") (pin "1") (pinfunction "1_1") (pintype "passive"))
      (node (ref "J1") (pin "3") (pinfunction "3_3") (pintype "input"))
      (node (ref "J1") (pin "7") (pinfunction "7_7") (pintype "input"))
      (node (ref "J1") (pin "8") (pinfunction "8_8") (pintype "input"))
      (node (ref "J1") (pin "GC") (pinfunction "C-G_GC") (pintype "passive"))
      (node (ref "J1") (pin "M1") (pinfunction "SHIELD_M1") (pintype "passive"))
      (node (ref "J1") (pin "M2") (pinfunction "SHIELD_M2") (pintype "passive"))
      (node (ref "J6") (pin "3") (pinfunction "3_3") (pintype "passive"))
      (node (ref "J6") (pin "4") (pinfunction "4_4") (pintype "passive"))
      (node (ref "U11") (pin "3") (pinfunction "GND_3") (pintype "passive"))
      (node (ref "U2") (pin "2") (pinfunction "GND_2") (pintype "power_in"))
      (node (ref "U2") (pin "8") (pinfunction "S_8") (pintype "input"))
      (node (ref "U3") (pin "5") (pinfunction "GND2_5") (pintype "power_in"))
      (node (ref "U4") (pin "2") (pinfunction "AC2_2") (pintype "passive"))
    )
    (net (code "17") (name "IN_A") (class "Default")
      (node (ref "R24") (pin "1") (pinfunction "1_1") (pintype "passive"))
      (node (ref "U1") (pin "12") (pinfunction "PA2_12") (pintype "bidirectional"))
    )
    (net (code "18") (name "IN_B") (class "Default")
      (node (ref "R17") (pin "1") (pinfunction "1_1") (pintype "passive"))
      (node (ref "U1") (pin "13") (pinfunction "PA3_13") (pintype "bidirectional"))
    )
    (net (code "19") (name "IN_HI_A") (class "Default")
      (node (ref "R18") (pin "1") (pinfunction "1_1") (pintype "passive"))
      (node (ref "U1") (pin "30") (pinfunction "PA9_30") (pintype "bidirectional"))
      (node (ref "U5") (pin "2") (pinfunction "IN_HI_2") (pintype "input"))
    )
    (net (code "20") (name "IN_HI_B") (class "Default")
      (node (ref "R19") (pin "1") (pinfunction "1_1") (pintype "passive"))
      (node (ref "U1") (pin "29") (pinfunction "PA8_29") (pintype "bidirectional"))
      (node (ref "U6") (pin "2") (pinfunction "IN_HI_2") (pintype "input"))
    )
    (net (code "21") (name "IN_LO_A") (class "Default")
      (node (ref "R22") (pin "1") (pinfunction "1_1") (pintype "passive"))
      (node (ref "U1") (pin "27") (pinfunction "PB14_27") (pintype "bidirectional"))
      (node (ref "U5") (pin "3") (pinfunction "IN_LO_3") (pintype "input"))
    )
    (net (code "22") (name "IN_LO_B") (class "Default")
      (node (ref "R23") (pin "1") (pinfunction "1_1") (pintype "passive"))
      (node (ref "U1") (pin "26") (pinfunction "PB13_26") (pintype "bidirectional"))
      (node (ref "U6") (pin "3") (pinfunction "IN_LO_3") (pintype "input"))
    )
    (net (code "23") (name "ISENSE") (class "Default")
      (node (ref "C16") (pin "2") (pinfunction "2_2") (pintype "passive"))
      (node (ref "R123") (pin "1") (pinfunction "1_1") (pintype "passive"))
      (node (ref "U1") (pin "14") (pinfunction "PA4_14") (pintype "bidirectional"))
    )
    (net (code "24") (name "JMP0") (class "Default")
      (node (ref "J5") (pin "9") (pinfunction "9_9") (pintype "passive"))
      (node (ref "U1") (pin "19") (pinfunction "PB1_19") (pintype "bidirectional"))
    )
    (net (code "25") (name "JMP1") (class "Default")
      (node (ref "J5") (pin "7") (pinfunction "7_7") (pintype "passive"))
      (node (ref "U1") (pin "20") (pinfunction "PB2-BOOT1_20") (pintype "bidirectional"))
    )
    (net (code "26") (name "JMP2") (class "Default")
      (node (ref "J5") (pin "5") (pinfunction "5_5") (pintype "passive"))
      (node (ref "U1") (pin "21") (pinfunction "PB10_21") (pintype "bidirectional"))
    )
    (net (code "27") (name "JMP3") (class "Default")
      (node (ref "J5") (pin "3") (pinfunction "3_3") (pintype "passive"))
      (node (ref "U1") (pin "22") (pinfunction "PB11_22") (pintype "bidirectional"))
    )
    (net (code "28") (name "JMP4") (class "Default")
      (node (ref "J5") (pin "1") (pinfunction "1_1") (pintype "passive"))
      (node (ref "U1") (pin "25") (pinfunction "PB12_25") (pintype "bidirectional"))
    )
    (net (code "29") (name "LED0") (class "Default")
      (node (ref "R109") (pin "1") (pinfunction "1_1") (pintype "passive"))
      (node (ref "U1") (pin "16") (pinfunction "PA6_16") (pintype "bidirectional"))
    )
    (net (code "30") (name "LED1") (class "Default")
      (node (ref "R110") (pin "1") (pinfunction "1_1") (pintype "passive"))
      (node (ref "U1") (pin "17") (pinfunction "PA7_17") (pintype "bidirectional"))
    )
    (net (code "31") (name "LED2") (class "Default")
      (node (ref "R111") (pin "1") (pinfunction "1_1") (pintype "passive"))
      (node (ref "U1") (pin "18") (pinfunction "PB0_18") (pintype "bidirectional"))
    )
    (net (code "32") (name "LED_CAN") (class "Default")
      (node (ref "R21") (pin "1") (pinfunction "1_1") (pintype "passive"))
      (node (ref "U1") (pin "3") (pinfunction "PC14-OSC32_IN_3") (pintype "bidirectional"))
    )
    (net (code "33") (name "Net-(D9-PadA)") (class "Default")
      (node (ref "D9") (pin "A") (pinfunction "A_A") (pintype "passive"))
      (node (ref "R109") (pin "2") (pinfunction "2_2") (pintype "passive"))
    )
    (net (code "34") (name "Net-(D10-PadA)") (class "Default")
      (node (ref "D10") (pin "A") (pinfunction "A_A") (pintype "passive"))
      (node (ref "R110") (pin "2") (pinfunction "2_2") (pintype "passive"))
    )
    (net (code "35") (name "Net-(D11-PadA)") (class "Default")
      (node (ref "D11") (pin "A") (pinfunction "A_A") (pintype "passive"))
      (node (ref "R111") (pin "2") (pinfunction "2_2") (pintype "passive"))
    )
    (net (code "36") (name "Net-(F1-Pad2)") (class "Default")
      (node (ref "F1") (pin "2") (pinfunction "2_2") (pintype "passive"))
      (node (ref "J1") (pin "4") (pinfunction "4_4") (pintype "input"))
      (node (ref "J1") (pin "5") (pinfunction "5_5") (pintype "input"))
      (node (ref "R20") (pin "1") (pinfunction "1_1") (pintype "passive"))
    )
    (net (code "37") (name "Net-(J1-A-G)") (class "Default")
      (node (ref "J1") (pin "GA") (pinfunction "A-G_GA") (pintype "passive"))
      (node (ref "R20") (pin "2") (pinfunction "2_2") (pintype "passive"))
    )
    (net (code "38") (name "Net-(J1-A-Y)") (class "Default")
      (node (ref "J1") (pin "YA") (pinfunction "A-Y_YA") (pintype "passive"))
      (node (ref "R21") (pin "2") (pinfunction "2_2") (pintype "passive"))
    )
    (net (code "39") (name "Net-(J2-Pad3)") (class "Default")
      (node (ref "J2") (pin "3") (pinfunction "3_3") (pintype "passive"))
      (node (ref "R15") (pin "2") (pinfunction "2_2") (pintype "passive"))
    )
    (net (code "40") (name "Net-(J2-Pad4)") (class "Default")
      (node (ref "J2") (pin "4") (pinfunction "4_4") (pintype "passive"))
      (node (ref "R16") (pin "2") (pinfunction "2_2") (pintype "passive"))
    )
    (net (code "41") (name "Net-(J3-Pad3)") (class "Default")
      (node (ref "J3") (pin "3") (pinfunction "3_3") (pintype "passive"))
      (node (ref "R24") (pin "2") (pinfunction "2_2") (pintype "passive"))
    )
    (net (code "42") (name "Net-(J3-Pad4)") (class "Default")
      (node (ref "J3") (pin "4") (pinfunction "4_4") (pintype "passive"))
      (node (ref "R17") (pin "2") (pinfunction "2_2") (pintype "passive"))
    )
    (net (code "43") (name "Net-(J6-Pad2)") (class "Default")
      (node (ref "J6") (pin "2") (pinfunction "2_2") (pintype "passive"))
      (node (ref "R12") (pin "2") (pinfunction "2_2") (pintype "passive"))
    )
    (net (code "44") (name "Net-(L1-1)") (class "Default")
      (node (ref "D5") (pin "C") (pinfunction "C_C") (pintype "passive"))
      (node (ref "L1") (pin "P$1") (pinfunction "1_P$1") (pintype "passive"))
      (node (ref "U12") (pin "2") (pinfunction "SWE_2") (pintype "passive"))
    )
    (net (code "45") (name "Net-(L2-1)") (class "Default")
      (node (ref "D6") (pin "C") (pinfunction "C_C") (pintype "passive"))
      (node (ref "L2") (pin "P$1") (pinfunction "1_P$1") (pintype "passive"))
      (node (ref "U9") (pin "2") (pinfunction "SWE_2") (pintype "passive"))
    )
    (net (code "46") (name "Net-(Q1-GATE)") (class "Default")
      (node (ref "Q1") (pin "4") (pinfunction "GATE_4") (pintype "passive"))
      (node (ref "R5") (pin "2") (pinfunction "2_2") (pintype "passive"))
      (node (ref "U5") (pin "7") (pinfunction "DRV_HI_7") (pintype "output"))
    )
    (net (code "47") (name "Net-(Q2-GATE)") (class "Default")
      (node (ref "Q2") (pin "4") (pinfunction "GATE_4") (pintype "passive"))
      (node (ref "R3") (pin "2") (pinfunction "2_2") (pintype "passive"))
    )
    (net (code "48") (name "Net-(Q3-GATE)") (class "Default")
      (node (ref "Q3") (pin "4") (pinfunction "GATE_4") (pintype "passive"))
      (node (ref "R6") (pin "2") (pinfunction "2_2") (pintype "passive"))
      (node (ref "U6") (pin "7") (pinfunction "DRV_HI_7") (pintype "output"))
    )
    (net (code "49") (name "Net-(Q4-GATE)") (class "Default")
      (node (ref "Q4") (pin "4") (pinfunction "GATE_4") (pintype "passive"))
      (node (ref "R4") (pin "2") (pinfunction "2_2") (pintype "passive"))
    )
    (net (code "50") (name "Net-(U1-OSC_IN)") (class "Default")
      (node (ref "U1") (pin "5") (pinfunction "OSC_IN_5") (pintype "input"))
      (node (ref "X1") (pin "1") (pinfunction "1_1") (pintype "passive"))
    )
    (net (code "51") (name "Net-(U1-OSC_OUT)") (class "Default")
      (node (ref "U1") (pin "6") (pinfunction "OSC_OUT_6") (pintype "output"))
      (node (ref "X1") (pin "3") (pinfunction "3_3") (pintype "passive"))
    )
    (net (code "52") (name "Net-(U2-RXD)") (class "Default")
      (node (ref "U2") (pin "4") (pinfunction "RXD_4") (pintype "output"))
      (node (ref "U3") (pin "6") (pinfunction "B2_6") (pintype "output"))
    )
    (net (code "53") (name "Net-(U2-TXD)") (class "Default")
      (node (ref "U2") (pin "1") (pinfunction "TXD_1") (pintype "input"))
      (node (ref "U3") (pin "7") (pinfunction "B1_7") (pintype "output"))
    )
    (net (code "54") (name "Net-(U4-AC1)") (class "Default")
      (node (ref "R28") (pin "1") (pinfunction "1_1") (pintype "passive"))
      (node (ref "U4") (pin "1") (pinfunction "AC1_1") (pintype "passive"))
    )
    (net (code "55") (name "Net-(U5-BRIDGE)") (class "Default")
      (node (ref "C9") (pin "2") (pinfunction "2_2") (pintype "passive"))
      (node (ref "D3") (pin "C") (pinfunction "C_C") (pintype "passive"))
      (node (ref "R1") (pin "1") (pinfunction "1_1") (pintype "passive"))
      (node (ref "U5") (pin "6") (pinfunction "BRIDGE_6") (pintype "power_in"))
    )
    (net (code "56") (name "Net-(U5-DRV_LO)") (class "Default")
      (node (ref "R3") (pin "1") (pinfunction "1_1") (pintype "passive"))
      (node (ref "R7") (pin "2") (pinfunction "2_2") (pintype "passive"))
      (node (ref "U5") (pin "5") (pinfunction "DRV_LO_5") (pintype "output"))
    )
    (net (code "57") (name "Net-(U5-VBOOT)") (class "Default")
      (node (ref "C9") (pin "1") (pinfunction "1_1") (pintype "passive"))
      (node (ref "D1") (pin "C") (pinfunction "C_C") (pintype "passive"))
      (node (ref "U5") (pin "8") (pinfunction "VBOOT_8") (pintype "power_in"))
    )
    (net (code "58") (name "Net-(U6-BRIDGE)") (class "Default")
      (node (ref "C10") (pin "2") (pinfunction "2_2") (pintype "passive"))
      (node (ref "D4") (pin "C") (pinfunction "C_C") (pintype "passive"))
      (node (ref "R2") (pin "1") (pinfunction "1_1") (pintype "passive"))
      (node (ref "U6") (pin "6") (pinfunction "BRIDGE_6") (pintype "power_in"))
    )
    (net (code "59") (name "Net-(U6-DRV_LO)") (class "Default")
      (node (ref "R4") (pin "1") (pinfunction "1_1") (pintype "passive"))
      (node (ref "R8") (pin "2") (pinfunction "2_2") (pintype "passive"))
      (node (ref "U6") (pin "5") (pinfunction "DRV_LO_5") (pintype "output"))
    )
    (net (code "60") (name "Net-(U6-VBOOT)") (class "Default")
      (node (ref "C10") (pin "1") (pinfunction "1_1") (pintype "passive"))
      (node (ref "D2") (pin "C") (pinfunction "C_C") (pintype "passive"))
      (node (ref "U6") (pin "8") (pinfunction "VBOOT_8") (pintype "power_in"))
    )
    (net (code "61") (name "Net-(U7-IN+)") (class "Default")
      (node (ref "C14") (pin "2") (pinfunction "2_2") (pintype "passive"))
      (node (ref "R10") (pin "2") (pinfunction "2_2") (pintype "passive"))
      (node (ref "U7") (pin "4") (pinfunction "IN+_4") (pintype "passive"))
    )
    (net (code "62") (name "Net-(U7-IN-)") (class "Default")
      (node (ref "C14") (pin "1") (pinfunction "1_1") (pintype "passive"))
      (node (ref "R11") (pin "2") (pinfunction "2_2") (pintype "passive"))
      (node (ref "U7") (pin "5") (pinfunction "IN-_5") (pintype "passive"))
    )
    (net (code "63") (name "Net-(U7-OUT)") (class "Default")
      (node (ref "R123") (pin "2") (pinfunction "2_2") (pintype "passive"))
      (node (ref "U7") (pin "6") (pinfunction "OUT_6") (pintype "passive"))
    )
    (net (code "64") (name "Net-(U9-DC)") (class "Default")
      (node (ref "R29") (pin "2") (pinfunction "2_2") (pintype "passive"))
      (node (ref "U9") (pin "1") (pinfunction "SWC_1") (pintype "passive"))
      (node (ref "U9") (pin "7") (pinfunction "IS_7") (pintype "passive"))
      (node (ref "U9") (pin "8") (pinfunction "DC_8") (pintype "passive"))
    )
    (net (code "65") (name "Net-(U9-FB)") (class "Default")
      (node (ref "R31") (pin "1") (pinfunction "1_1") (pintype "passive"))
      (node (ref "R32") (pin "2") (pinfunction "2_2") (pintype "passive"))
      (node (ref "U9") (pin "5") (pinfunction "FB_5") (pintype "passive"))
    )
    (net (code "66") (name "Net-(U9-TC)") (class "Default")
      (node (ref "C39") (pin "1") (pinfunction "1_1") (pintype "passive"))
      (node (ref "U9") (pin "3") (pinfunction "TC_3") (pintype "passive"))
    )
    (net (code "67") (name "Net-(U12-DC)") (class "Default")
      (node (ref "R25") (pin "2") (pinfunction "2_2") (pintype "passive"))
      (node (ref "U12") (pin "1") (pinfunction "SWC_1") (pintype "passive"))
      (node (ref "U12") (pin "7") (pinfunction "IS_7") (pintype "passive"))
      (node (ref "U12") (pin "8") (pinfunction "DC_8") (pintype "passive"))
    )
    (net (code "68") (name "Net-(U12-FB)") (class "Default")
      (node (ref "R26") (pin "1") (pinfunction "1_1") (pintype "passive"))
      (node (ref "R27") (pin "2") (pinfunction "2_2") (pintype "passive"))
      (node (ref "U12") (pin "5") (pinfunction "FB_5") (pintype "passive"))
    )
    (net (code "69") (name "Net-(U12-TC)") (class "Default")
      (node (ref "C37") (pin "1") (pinfunction "1_1") (pintype "passive"))
      (node (ref "U12") (pin "3") (pinfunction "TC_3") (pintype "passive"))
    )
    (net (code "70") (name "SWCLK") (class "Default")
      (node (ref "J4") (pin "4") (pinfunction "4_4") (pintype "passive"))
      (node (ref "U1") (pin "37") (pinfunction "PA14-JTCK-SWCLK_37") (pintype "bidirectional"))
    )
    (net (code "71") (name "SWDIO") (class "Default")
      (node (ref "J4") (pin "6") (pinfunction "6_6") (pintype "passive"))
      (node (ref "U1") (pin "34") (pinfunction "PA13-JTMS-SWDIO_34") (pintype "bidirectional"))
    )
    (net (code "72") (name "UART_RX") (class "Default")
      (node (ref "J4") (pin "1") (pinfunction "1_1") (pintype "passive"))
      (node (ref "U1") (pin "43") (pinfunction "PB7_43") (pintype "bidirectional"))
    )
    (net (code "73") (name "UART_TX") (class "Default")
      (node (ref "J4") (pin "3") (pinfunction "3_3") (pintype "passive"))
      (node (ref "U1") (pin "42") (pinfunction "PB6_42") (pintype "bidirectional"))
    )
    (net (code "74") (name "VCC") (class "Default")
      (node (ref "C1") (pin "+") (pinfunction "+_+") (pintype "passive"))
      (node (ref "C11") (pin "1") (pinfunction "1_1") (pintype "passive"))
      (node (ref "C12") (pin "1") (pinfunction "1_1") (pintype "passive"))
      (node (ref "C2") (pin "+") (pinfunction "+_+") (pintype "passive"))
      (node (ref "C3") (pin "1") (pinfunction "1_1") (pintype "passive"))
      (node (ref "C38") (pin "+") (pinfunction "+_+") (pintype "passive"))
      (node (ref "C40") (pin "+") (pinfunction "+_+") (pintype "passive"))
      (node (ref "C5") (pin "1") (pinfunction "1_1") (pintype "passive"))
      (node (ref "C6") (pin "1") (pinfunction "1_1") (pintype "passive"))
      (node (ref "Q1") (pin "5") (pinfunction "DRAIN_5") (pintype "passive"))
      (node (ref "Q3") (pin "5") (pinfunction "DRAIN_5") (pintype "passive"))
      (node (ref "R13") (pin "2") (pinfunction "2_2") (pintype "passive"))
      (node (ref "R25") (pin "1") (pinfunction "1_1") (pintype "passive"))
      (node (ref "R29") (pin "1") (pinfunction "1_1") (pintype "passive"))
      (node (ref "U12") (pin "6") (pinfunction "VCC_6") (pintype "passive"))
      (node (ref "U9") (pin "6") (pinfunction "VCC_6") (pintype "passive"))
    )
    (net (code "75") (name "VCS") (class "Default")
      (node (ref "C11") (pin "2") (pinfunction "2_2") (pintype "passive"))
      (node (ref "C12") (pin "2") (pinfunction "2_2") (pintype "passive"))
      (node (ref "C13") (pin "2") (pinfunction "2_2") (pintype "passive"))
      (node (ref "C5") (pin "2") (pinfunction "2_2") (pintype "passive"))
      (node (ref "C6") (pin "2") (pinfunction "2_2") (pintype "passive"))
      (node (ref "Q2") (pin "1") (pinfunction "SOURCE_1") (pintype "passive"))
      (node (ref "Q2") (pin "2") (pinfunction "SOURCE_2") (pintype "passive"))
      (node (ref "Q2") (pin "3") (pinfunction "SOURCE_3") (pintype "passive"))
      (node (ref "Q4") (pin "1") (pinfunction "SOURCE_1") (pintype "passive"))
      (node (ref "Q4") (pin "2") (pinfunction "SOURCE_2") (pintype "passive"))
      (node (ref "Q4") (pin "3") (pinfunction "SOURCE_3") (pintype "passive"))
      (node (ref "R7") (pin "1") (pinfunction "1_1") (pintype "passive"))
      (node (ref "R8") (pin "1") (pinfunction "1_1") (pintype "passive"))
      (node (ref "R9") (pin "2$1") (pinfunction "2_2$1") (pintype "passive"))
      (node (ref "R9") (pin "2$2") (pinfunction "2_2$2") (pintype "passive"))
    )
    (net (code "76") (name "VCS_B_N") (class "Default")
      (node (ref "R11") (pin "1") (pinfunction "1_1") (pintype "passive"))
      (node (ref "R9") (pin "1S") (pinfunction "1S_1S") (pintype "passive"))
    )
    (net (code "77") (name "VCS_B_P") (class "Default")
      (node (ref "R10") (pin "1") (pinfunction "1_1") (pintype "passive"))
      (node (ref "R9") (pin "2S") (pinfunction "2S_2S") (pintype "passive"))
    )
    (net (code "78") (name "VSENSE") (class "Default")
      (node (ref "C17") (pin "2") (pinfunction "2_2") (pintype "passive"))
      (node (ref "R13") (pin "1") (pinfunction "1_1") (pintype "passive"))
      (node (ref "R14") (pin "2") (pinfunction "2_2") (pintype "passive"))
      (node (ref "U1") (pin "15") (pinfunction "PA5_15") (pintype "bidirectional"))
    )
    (net (code "79") (name "unconnected-(U1-PA10-Pad31)") (class "Default")
      (node (ref "U1") (pin "31") (pinfunction "PA10_31") (pintype "bidirectional"))
    )
    (net (code "80") (name "unconnected-(U1-PA11-Pad32)") (class "Default")
      (node (ref "U1") (pin "32") (pinfunction "PA11_32") (pintype "bidirectional"))
    )
    (net (code "81") (name "unconnected-(U1-PA12-Pad33)") (class "Default")
      (node (ref "U1") (pin "33") (pinfunction "PA12_33") (pintype "bidirectional"))
    )
    (net (code "82") (name "unconnected-(U1-PA15-JTDI-Pad38)") (class "Default")
      (node (ref "U1") (pin "38") (pinfunction "PA15-JTDI_38") (pintype "bidirectional"))
    )
    (net (code "83") (name "unconnected-(U1-PB3-JTDO-Pad39)") (class "Default")
      (node (ref "U1") (pin "39") (pinfunction "PB3-JTDO_39") (pintype "bidirectional"))
    )
    (net (code "84") (name "unconnected-(U1-PB4-JNTRST-Pad40)") (class "Default")
      (node (ref "U1") (pin "40") (pinfunction "PB4-JNTRST_40") (pintype "bidirectional"))
    )
    (net (code "85") (name "unconnected-(U1-PB5-Pad41)") (class "Default")
      (node (ref "U1") (pin "41") (pinfunction "PB5_41") (pintype "bidirectional"))
    )
    (net (code "86") (name "unconnected-(U1-PB15-Pad28)") (class "Default")
      (node (ref "U1") (pin "28") (pinfunction "PB15_28") (pintype "bidirectional"))
    )
    (net (code "87") (name "unconnected-(U1-PC15-OSC32_OUT-Pad4)") (class "Default")
      (node (ref "U1") (pin "4") (pinfunction "PC15-OSC32_OUT_4") (pintype "bidirectional"))
    )
    (net (code "88") (name "unconnected-(U1-VBAT-Pad1)") (class "Default")
      (node (ref "U1") (pin "1") (pinfunction "VBAT_1") (pintype "passive"))
    )
    (net (code "89") (name "~{EMS_ISO}") (class "Default")
      (node (ref "J1") (pin "6") (pinfunction "6_6") (pintype "input"))
      (node (ref "R28") (pin "2") (pinfunction "2_2") (pintype "passive"))
    )
    (net (code "90") (name "~{EMS}") (class "Default")
      (node (ref "R30") (pin "2") (pinfunction "2_2") (pintype "passive"))
      (node (ref "U1") (pin "2") (pinfunction "PC13-TAMPER-RTC_2") (pintype "bidirectional"))
      (node (ref "U4") (pin "3") (pinfunction "E_3") (pintype "passive"))
    )
    (net (code "91") (name "~{RESET}") (class "Default")
      (node (ref "C22") (pin "2") (pinfunction "2_2") (pintype "passive"))
      (node (ref "S1") (pin "P$2") (pinfunction "2_P$2") (pintype "bidirectional"))
      (node (ref "U1") (pin "7") (pinfunction "NRST_7") (pintype "bidirectional"))
    )
  )
)
